# Ideal_Diode_test.net
KiCad netlist of a schematic drawn in EAGLE
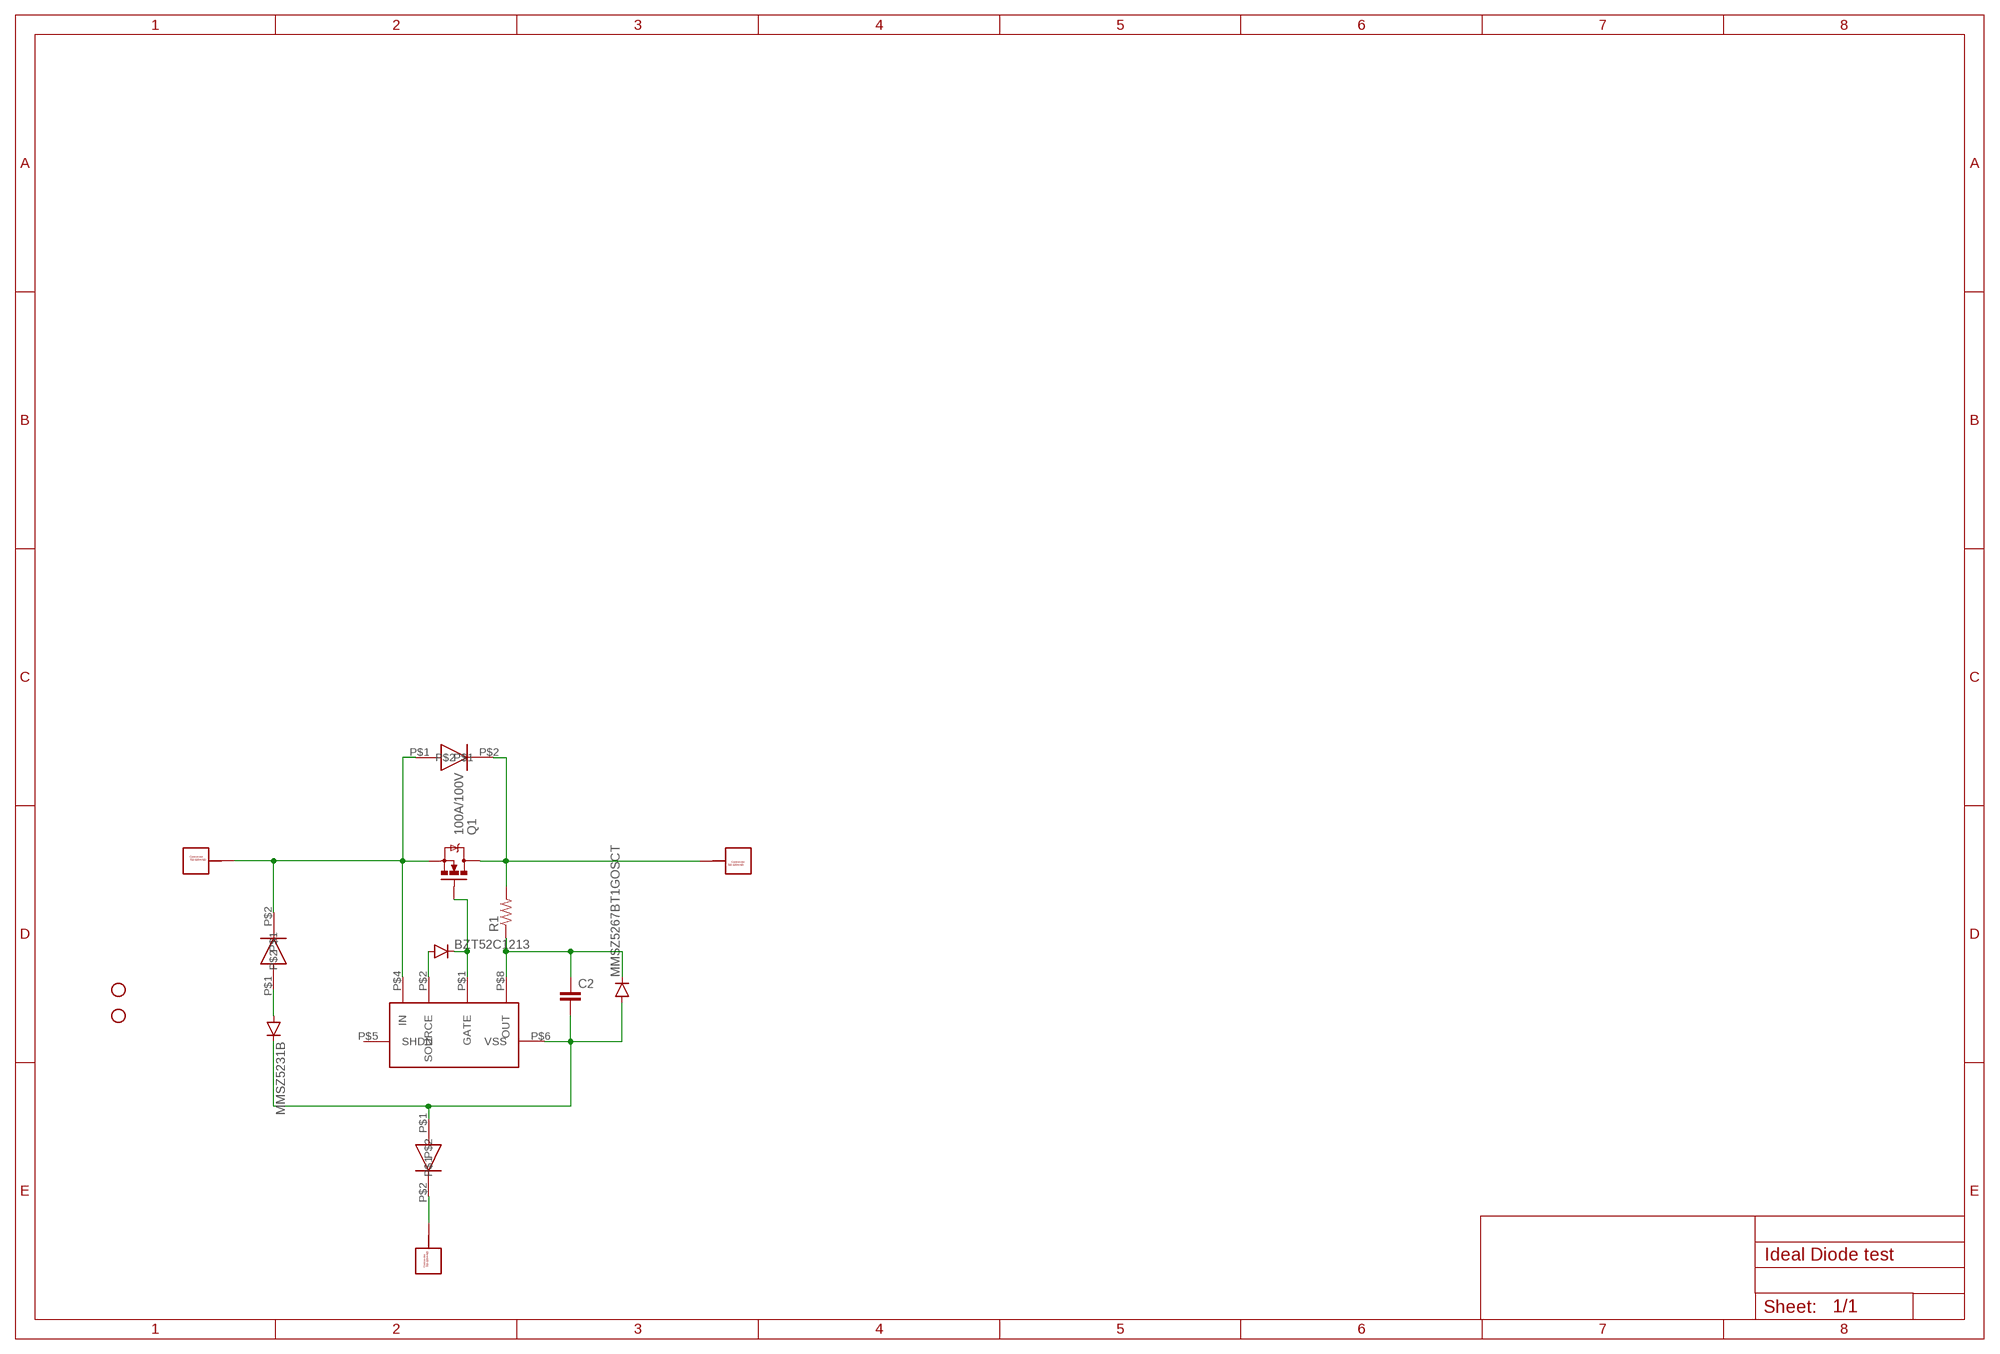
[diagram p0: schematic, sheet 1]

(export (version "E")
  (design (tool "Eeschema 10.0.6"))
  (components
    (comp (ref "BZT52C1213")
      (value "DIODESOD123")
      (footprint "eagle-import:SOD-123")
      (libsource (lib "eagle-import") (part "DIODESOD123"))
    )
    (comp (ref "C2")
      (value "CAP0603-CAP")
      (footprint "eagle-import:0603-CAP")
      (libsource (lib "eagle-import") (part "CAP0603-CAP"))
    )
    (comp (ref "MMSZ5231B")
      (value "DIODESOD123")
      (footprint "eagle-import:SOD-123")
      (libsource (lib "eagle-import") (part "DIODESOD123"))
    )
    (comp (ref "MMSZ5267BT1GOSCT")
      (value "DIODESOD123")
      (footprint "eagle-import:SOD-123")
      (libsource (lib "eagle-import") (part "DIODESOD123"))
    )
    (comp (ref "Q1")
      (value "100A/100V")
      (footprint "eagle-import:TO-263_D2PAK")
      (libsource (lib "eagle-import") (part "MOSFET-NCHANNELPSMN7R0"))
    )
    (comp (ref "R1")
      (value "RESISTOR0603-RES")
      (footprint "eagle-import:0603-RES")
      (libsource (lib "eagle-import") (part "RESISTOR0603-RES"))
    )
    (comp (ref "S1B")
      (value "DIODE")
      (footprint "eagle-import:SMA")
      (libsource (lib "eagle-import") (part "DIODE"))
    )
    (comp (ref "SMAJ70A")
      (value "DIODE")
      (footprint "eagle-import:SMA")
      (libsource (lib "eagle-import") (part "DIODE"))
    )
    (comp (ref "SMAJ150A")
      (value "DIODE")
      (footprint "eagle-import:SMA")
      (libsource (lib "eagle-import") (part "DIODE"))
    )
    (comp (ref "STANDOFF1")
      (value "STAND-OFF")
      (footprint "eagle-import:STAND-OFF")
      (libsource (lib "eagle-import") (part "STAND-OFF"))
    )
    (comp (ref "STANDOFF2")
      (value "STAND-OFF")
      (footprint "eagle-import:STAND-OFF")
      (libsource (lib "eagle-import") (part "STAND-OFF"))
    )
    (comp (ref "U$1")
      (value "LTC359")
      (footprint "eagle-import:LTC4359")
      (libsource (lib "eagle-import") (part "LTC359"))
    )
    (comp (ref "U$2")
      (value "732-3204-ND_CONNECTOR")
      (footprint "eagle-import:732-3204-ND")
      (libsource (lib "eagle-import") (part "732-3204-ND_CONNECTOR"))
    )
    (comp (ref "U$3")
      (value "732-3204-ND_CONNECTOR")
      (footprint "eagle-import:732-3204-ND")
      (libsource (lib "eagle-import") (part "732-3204-ND_CONNECTOR"))
    )
    (comp (ref "U$4")
      (value "732-3204-ND_CONNECTOR")
      (footprint "eagle-import:732-3204-ND")
      (libsource (lib "eagle-import") (part "732-3204-ND_CONNECTOR"))
    )
  )
  (nets
    (net (code "1") (name "Net-(MMSZ5231B-PadA)") (class "Default")
      (node (ref "MMSZ5231B") (pin "A") (pinfunction "A_A") (pintype "passive"))
      (node (ref "SMAJ70A") (pin "P$1") (pinfunction "P$1_P$1") (pintype "bidirectional"))
    )
    (net (code "2") (name "Net-(Q1-D)") (class "Default")
      (node (ref "Q1") (pin "2") (pinfunction "D_2") (pintype "passive"))
      (node (ref "R1") (pin "2") (pinfunction "2_2") (pintype "passive"))
      (node (ref "SMAJ150A") (pin "P$2") (pinfunction "P$2_P$2") (pintype "bidirectional"))
      (node (ref "U$2") (pin "P$1") (pinfunction "P$1_P$1") (pintype "bidirectional"))
      (node (ref "U$2") (pin "P$10") (pinfunction "P$1_P$10") (pintype "bidirectional"))
      (node (ref "U$2") (pin "P$2") (pinfunction "P$1_P$2") (pintype "bidirectional"))
      (node (ref "U$2") (pin "P$3") (pinfunction "P$1_P$3") (pintype "bidirectional"))
      (node (ref "U$2") (pin "P$4") (pinfunction "P$1_P$4") (pintype "bidirectional"))
      (node (ref "U$2") (pin "P$5") (pinfunction "P$1_P$5") (pintype "bidirectional"))
      (node (ref "U$2") (pin "P$6") (pinfunction "P$1_P$6") (pintype "bidirectional"))
      (node (ref "U$2") (pin "P$7") (pinfunction "P$1_P$7") (pintype "bidirectional"))
      (node (ref "U$2") (pin "P$8") (pinfunction "P$1_P$8") (pintype "bidirectional"))
      (node (ref "U$2") (pin "P$9") (pinfunction "P$1_P$9") (pintype "bidirectional"))
    )
    (net (code "3") (name "Net-(Q1-G)") (class "Default")
      (node (ref "BZT52C1213") (pin "C") (pinfunction "C_C") (pintype "passive"))
      (node (ref "Q1") (pin "1") (pinfunction "G_1") (pintype "passive"))
      (node (ref "U$1") (pin "P$1") (pinfunction "GATE_P$1") (pintype "bidirectional"))
    )
    (net (code "4") (name "Net-(Q1-S)") (class "Default")
      (node (ref "Q1") (pin "3") (pinfunction "S_3") (pintype "passive"))
      (node (ref "SMAJ150A") (pin "P$1") (pinfunction "P$1_P$1") (pintype "bidirectional"))
      (node (ref "SMAJ70A") (pin "P$2") (pinfunction "P$2_P$2") (pintype "bidirectional"))
      (node (ref "U$1") (pin "P$4") (pinfunction "IN_P$4") (pintype "bidirectional"))
      (node (ref "U$3") (pin "P$1") (pinfunction "P$1_P$1") (pintype "bidirectional"))
      (node (ref "U$3") (pin "P$10") (pinfunction "P$1_P$10") (pintype "bidirectional"))
      (node (ref "U$3") (pin "P$2") (pinfunction "P$1_P$2") (pintype "bidirectional"))
      (node (ref "U$3") (pin "P$3") (pinfunction "P$1_P$3") (pintype "bidirectional"))
      (node (ref "U$3") (pin "P$4") (pinfunction "P$1_P$4") (pintype "bidirectional"))
      (node (ref "U$3") (pin "P$5") (pinfunction "P$1_P$5") (pintype "bidirectional"))
      (node (ref "U$3") (pin "P$6") (pinfunction "P$1_P$6") (pintype "bidirectional"))
      (node (ref "U$3") (pin "P$7") (pinfunction "P$1_P$7") (pintype "bidirectional"))
      (node (ref "U$3") (pin "P$8") (pinfunction "P$1_P$8") (pintype "bidirectional"))
      (node (ref "U$3") (pin "P$9") (pinfunction "P$1_P$9") (pintype "bidirectional"))
    )
    (net (code "5") (name "Net-(S1B-PadP$2)") (class "Default")
      (node (ref "S1B") (pin "P$2") (pinfunction "P$2_P$2") (pintype "bidirectional"))
      (node (ref "U$4") (pin "P$1") (pinfunction "P$1_P$1") (pintype "bidirectional"))
      (node (ref "U$4") (pin "P$10") (pinfunction "P$1_P$10") (pintype "bidirectional"))
      (node (ref "U$4") (pin "P$2") (pinfunction "P$1_P$2") (pintype "bidirectional"))
      (node (ref "U$4") (pin "P$3") (pinfunction "P$1_P$3") (pintype "bidirectional"))
      (node (ref "U$4") (pin "P$4") (pinfunction "P$1_P$4") (pintype "bidirectional"))
      (node (ref "U$4") (pin "P$5") (pinfunction "P$1_P$5") (pintype "bidirectional"))
      (node (ref "U$4") (pin "P$6") (pinfunction "P$1_P$6") (pintype "bidirectional"))
      (node (ref "U$4") (pin "P$7") (pinfunction "P$1_P$7") (pintype "bidirectional"))
      (node (ref "U$4") (pin "P$8") (pinfunction "P$1_P$8") (pintype "bidirectional"))
      (node (ref "U$4") (pin "P$9") (pinfunction "P$1_P$9") (pintype "bidirectional"))
    )
    (net (code "6") (name "Net-(U$1-OUT)") (class "Default")
      (node (ref "C2") (pin "1") (pinfunction "1_1") (pintype "passive"))
      (node (ref "MMSZ5267BT1GOSCT") (pin "C") (pinfunction "C_C") (pintype "passive"))
      (node (ref "R1") (pin "1") (pinfunction "1_1") (pintype "passive"))
      (node (ref "U$1") (pin "P$8") (pinfunction "OUT_P$8") (pintype "bidirectional"))
    )
    (net (code "7") (name "Net-(U$1-SOURCE)") (class "Default")
      (node (ref "BZT52C1213") (pin "A") (pinfunction "A_A") (pintype "passive"))
      (node (ref "U$1") (pin "P$2") (pinfunction "SOURCE_P$2") (pintype "bidirectional"))
    )
    (net (code "8") (name "Net-(U$1-VSS)") (class "Default")
      (node (ref "C2") (pin "2") (pinfunction "2_2") (pintype "passive"))
      (node (ref "MMSZ5231B") (pin "C") (pinfunction "C_C") (pintype "passive"))
      (node (ref "MMSZ5267BT1GOSCT") (pin "A") (pinfunction "A_A") (pintype "passive"))
      (node (ref "S1B") (pin "P$1") (pinfunction "P$1_P$1") (pintype "bidirectional"))
      (node (ref "U$1") (pin "P$6") (pinfunction "VSS_P$6") (pintype "bidirectional"))
    )
    (net (code "9") (name "unconnected-(U$1-SHDN-PadP$5)") (class "Default")
      (node (ref "U$1") (pin "P$5") (pinfunction "SHDN_P$5") (pintype "bidirectional"))
    )
  )
)
